# 1-Axis_Board_-_Camera_Gantry.net
KiCad netlist of a schematic drawn in EAGLE
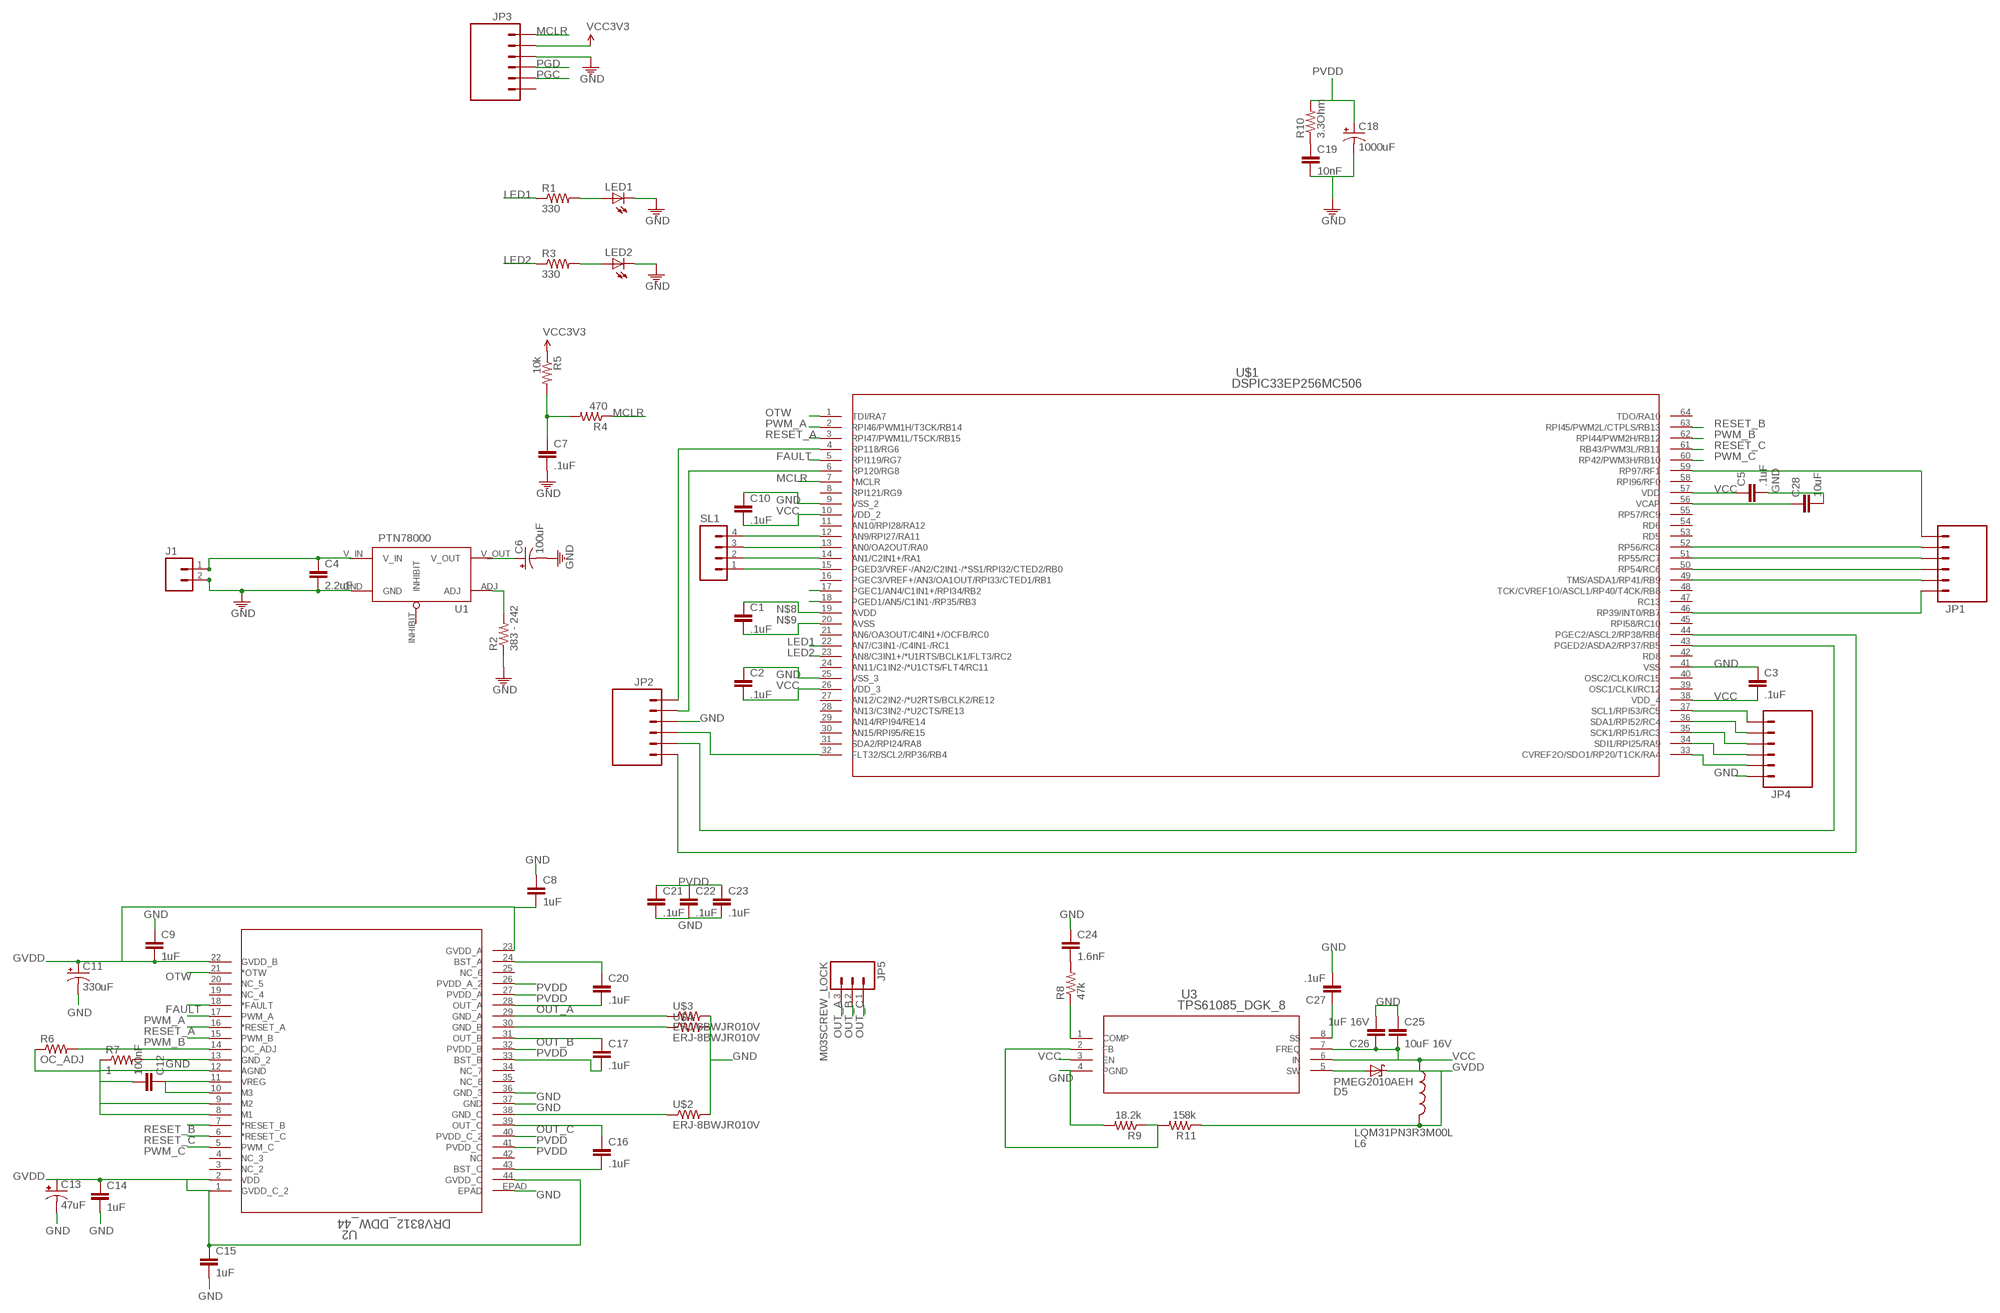
[diagram p0: schematic, sheet 1]

(export (version "E")
  (design (tool "Eeschema 10.0.6"))
  (components
    (comp (ref "C1")
      (value ".1uF")
      (footprint "eagle-import:0805")
      (libsource (lib "eagle-import") (part "CAP0805"))
    )
    (comp (ref "C2")
      (value ".1uF")
      (footprint "eagle-import:0805")
      (libsource (lib "eagle-import") (part "CAP0805"))
    )
    (comp (ref "C3")
      (value ".1uF")
      (footprint "eagle-import:0805")
      (libsource (lib "eagle-import") (part "CAP0805"))
    )
    (comp (ref "C4")
      (value "2.2uF")
      (footprint "eagle-import:1206")
      (libsource (lib "eagle-import") (part "CMPE118lib_CAP1206"))
    )
    (comp (ref "C5")
      (value ".1uF")
      (footprint "eagle-import:0805")
      (libsource (lib "eagle-import") (part "CAP0805"))
    )
    (comp (ref "C6")
      (value "100uF")
      (footprint "eagle-import:CPOL-RADIAL-100UF-25V")
      (libsource (lib "eagle-import") (part "CAP_POLPTH1"))
    )
    (comp (ref "C7")
      (value ".1uF")
      (footprint "eagle-import:0805")
      (libsource (lib "eagle-import") (part "CAP0805"))
    )
    (comp (ref "C8")
      (value "1uF")
      (footprint "eagle-import:0805")
      (libsource (lib "eagle-import") (part "CAP0805"))
    )
    (comp (ref "C9")
      (value "1uF")
      (footprint "eagle-import:0805")
      (libsource (lib "eagle-import") (part "CAP0805"))
    )
    (comp (ref "C10")
      (value ".1uF")
      (footprint "eagle-import:0805")
      (libsource (lib "eagle-import") (part "CAP0805"))
    )
    (comp (ref "C11")
      (value "330uF")
      (footprint "eagle-import:CPOL-RADIAL-1000UF-25V")
      (libsource (lib "eagle-import") (part "CAP_POLPTH4"))
    )
    (comp (ref "C12")
      (value "100nF")
      (footprint "eagle-import:0805")
      (libsource (lib "eagle-import") (part "CAP0805"))
    )
    (comp (ref "C13")
      (value "47uF")
      (footprint "eagle-import:CPOL-RADIAL-1000UF-25V")
      (libsource (lib "eagle-import") (part "CAP_POLPTH4"))
    )
    (comp (ref "C14")
      (value "1uF")
      (footprint "eagle-import:0805")
      (libsource (lib "eagle-import") (part "CAP0805"))
    )
    (comp (ref "C15")
      (value "1uF")
      (footprint "eagle-import:0805")
      (libsource (lib "eagle-import") (part "CAP0805"))
    )
    (comp (ref "C16")
      (value ".1uF")
      (footprint "eagle-import:0805")
      (libsource (lib "eagle-import") (part "CAP0805"))
    )
    (comp (ref "C17")
      (value ".1uF")
      (footprint "eagle-import:0805")
      (libsource (lib "eagle-import") (part "CAP0805"))
    )
    (comp (ref "C18")
      (value "1000uF")
      (footprint "eagle-import:CPOL-RADIAL-1000UF-25V")
      (libsource (lib "eagle-import") (part "CAP_POLPTH4"))
    )
    (comp (ref "C19")
      (value "10nF")
      (footprint "eagle-import:0805")
      (libsource (lib "eagle-import") (part "CAP0805"))
    )
    (comp (ref "C20")
      (value ".1uF")
      (footprint "eagle-import:0805")
      (libsource (lib "eagle-import") (part "CAP0805"))
    )
    (comp (ref "C21")
      (value ".1uF")
      (footprint "eagle-import:0805")
      (libsource (lib "eagle-import") (part "CAP0805"))
    )
    (comp (ref "C22")
      (value ".1uF")
      (footprint "eagle-import:0805")
      (libsource (lib "eagle-import") (part "CAP0805"))
    )
    (comp (ref "C23")
      (value ".1uF")
      (footprint "eagle-import:0805")
      (libsource (lib "eagle-import") (part "CAP0805"))
    )
    (comp (ref "C24")
      (value "1.6nF")
      (footprint "eagle-import:0805")
      (libsource (lib "eagle-import") (part "CAP0805"))
    )
    (comp (ref "C25")
      (value "10uF 16V")
      (footprint "eagle-import:1206")
      (libsource (lib "eagle-import") (part "CAP1206"))
    )
    (comp (ref "C26")
      (value "1uF 16V")
      (footprint "eagle-import:0805")
      (libsource (lib "eagle-import") (part "CAP0805"))
    )
    (comp (ref "C27")
      (value ".1uF")
      (footprint "eagle-import:0805")
      (libsource (lib "eagle-import") (part "CAP0805"))
    )
    (comp (ref "C28")
      (value "10uF")
      (footprint "eagle-import:1206")
      (libsource (lib "eagle-import") (part "CAP1206"))
    )
    (comp (ref "D5")
      (value "PMEG2010AEH")
      (footprint "eagle-import:SOD-123")
      (libsource (lib "eagle-import") (part "PMEG2010AEH"))
    )
    (comp (ref "J1")
      (value "M023.5MM-NO_SILK")
      (footprint "eagle-import:SCREWTERMINAL-3.5MM-2-NS")
      (libsource (lib "eagle-import") (part "M023.5MM-NO_SILK"))
    )
    (comp (ref "JP1")
      (value "M06LOCK")
      (footprint "eagle-import:1X06_LOCK")
      (libsource (lib "eagle-import") (part "M06LOCK"))
    )
    (comp (ref "JP2")
      (value "M06LOCK")
      (footprint "eagle-import:1X06_LOCK")
      (libsource (lib "eagle-import") (part "M06LOCK"))
    )
    (comp (ref "JP3")
      (value "M06LOCK")
      (footprint "eagle-import:1X06_LOCK")
      (libsource (lib "eagle-import") (part "CMPE118lib_M06LOCK"))
    )
    (comp (ref "JP4")
      (value "M06LOCK")
      (footprint "eagle-import:1X06_LOCK")
      (libsource (lib "eagle-import") (part "M06LOCK"))
    )
    (comp (ref "JP5")
      (value "M03SCREW_LOCK")
      (footprint "eagle-import:SCREWTERMINAL-3.5MM-3_LOCK.007S")
      (libsource (lib "eagle-import") (part "M03SCREW_LOCK"))
    )
    (comp (ref "L6")
      (value "LQM31PN3R3M00L")
      (footprint "eagle-import:1206")
      (libsource (lib "eagle-import") (part "LQM31PN3R3M00L"))
    )
    (comp (ref "LED1")
      (value "LED1206")
      (footprint "eagle-import:LED-1206")
      (fields (field (name "COLOR") "red"))
      (libsource (lib "eagle-import") (part "LED1206"))
    )
    (comp (ref "LED2")
      (value "LED1206")
      (footprint "eagle-import:LED-1206")
      (fields (field (name "COLOR") "red"))
      (libsource (lib "eagle-import") (part "LED1206"))
    )
    (comp (ref "R1")
      (value "330")
      (footprint "eagle-import:0805")
      (libsource (lib "eagle-import") (part "CMPE118lib_RESISTOR0805-RES"))
    )
    (comp (ref "R2")
      (value "383 - 242")
      (footprint "eagle-import:0805")
      (libsource (lib "eagle-import") (part "CMPE118lib_RESISTOR0805-RES"))
    )
    (comp (ref "R3")
      (value "330")
      (footprint "eagle-import:0805")
      (libsource (lib "eagle-import") (part "CMPE118lib_RESISTOR0805-RES"))
    )
    (comp (ref "R4")
      (value "470")
      (footprint "eagle-import:0805")
      (libsource (lib "eagle-import") (part "CMPE118lib_RESISTOR0805-RES"))
    )
    (comp (ref "R5")
      (value "10k")
      (footprint "eagle-import:0805")
      (libsource (lib "eagle-import") (part "CMPE118lib_RESISTOR0805-RES"))
    )
    (comp (ref "R6")
      (value "OC_ADJ")
      (footprint "eagle-import:0805")
      (libsource (lib "eagle-import") (part "RESISTOR0805-RES"))
    )
    (comp (ref "R7")
      (value "1")
      (footprint "eagle-import:0805")
      (libsource (lib "eagle-import") (part "RESISTOR0805-RES"))
    )
    (comp (ref "R8")
      (value "47k")
      (footprint "eagle-import:0805")
      (libsource (lib "eagle-import") (part "RESISTOR0805-RES"))
    )
    (comp (ref "R9")
      (value "18.2k")
      (footprint "eagle-import:0805")
      (libsource (lib "eagle-import") (part "RESISTOR0805-RES"))
    )
    (comp (ref "R10")
      (value "3.3Ohm")
      (footprint "eagle-import:0805")
      (libsource (lib "eagle-import") (part "RESISTOR0805-RES"))
    )
    (comp (ref "R11")
      (value "158k")
      (footprint "eagle-import:0805")
      (libsource (lib "eagle-import") (part "RESISTOR0805-RES"))
    )
    (comp (ref "SL1")
      (value "M04LOCK")
      (footprint "eagle-import:1X04_LOCK")
      (libsource (lib "eagle-import") (part "M04LOCK"))
    )
    (comp (ref "U$1")
      (value "DSPIC33EP256MC506")
      (footprint "eagle-import:QFP64-10X10MC")
      (libsource (lib "eagle-import") (part "DSPIC33EP256MC506"))
    )
    (comp (ref "U$2")
      (value "ERJ-8BWJR010V")
      (footprint "eagle-import:1206")
      (libsource (lib "eagle-import") (part "ERJ-8BWJR010V"))
    )
    (comp (ref "U$3")
      (value "ERJ-8BWJR010V")
      (footprint "eagle-import:1206")
      (libsource (lib "eagle-import") (part "ERJ-8BWJR010V"))
    )
    (comp (ref "U$4")
      (value "ERJ-8BWJR010V")
      (footprint "eagle-import:1206")
      (libsource (lib "eagle-import") (part "ERJ-8BWJR010V"))
    )
    (comp (ref "U1")
      (value "PTN78000")
      (footprint "eagle-import:PTN78000")
      (libsource (lib "eagle-import") (part "PTN78000THROUGH-HOLE"))
    )
    (comp (ref "U2")
      (value "DRV8312_DDW_44")
      (footprint "eagle-import:DDW44_8P26X4P31")
      (fields
        (field (name "GENERIC_PART_NUMBER") "DRV8312")
        (field (name "MANUFACTURER") "Texas Instruments")
        (field (name "MANUFACTURER_PART_NUMBER") "drv8312_ddw_44")
      )
      (libsource (lib "eagle-import") (part "DRV8312_DDW_44"))
    )
    (comp (ref "U3")
      (value "TPS61085_DGK_8")
      (footprint "eagle-import:DGK8")
      (fields
        (field (name "GENERIC_PART_NUMBER") "TPS61085")
        (field (name "MANUFACTURER") "Texas Instruments")
        (field (name "MANUFACTURER_PART_NUMBER") "tps61085_dgk_8")
      )
      (libsource (lib "eagle-import") (part "TPS61085_DGK_8"))
    )
  )
  (nets
    (net (code "1") (name "/FAULT") (class "Default")
      (node (ref "U$1") (pin "5") (pinfunction "RPI119/RG7_5") (pintype "passive"))
      (node (ref "U2") (pin "18") (pinfunction "*FAULT_18") (pintype "output"))
    )
    (net (code "2") (name "/GVDD") (class "Default")
      (node (ref "C11") (pin "1") (pinfunction "+_1") (pintype "passive"))
      (node (ref "C13") (pin "1") (pinfunction "+_1") (pintype "passive"))
      (node (ref "C14") (pin "1") (pinfunction "1_1") (pintype "passive"))
      (node (ref "C15") (pin "1") (pinfunction "1_1") (pintype "passive"))
      (node (ref "C8") (pin "2") (pinfunction "2_2") (pintype "passive"))
      (node (ref "C9") (pin "2") (pinfunction "2_2") (pintype "passive"))
      (node (ref "D5") (pin "C") (pinfunction "C_C") (pintype "passive"))
      (node (ref "L6") (pin "2") (pinfunction "2_2") (pintype "passive"))
      (node (ref "R11") (pin "1") (pinfunction "1_1") (pintype "passive"))
      (node (ref "U2") (pin "1") (pinfunction "GVDD_C_2_1") (pintype "power_in"))
      (node (ref "U2") (pin "2") (pinfunction "VDD_2") (pintype "power_in"))
      (node (ref "U2") (pin "22") (pinfunction "GVDD_B_22") (pintype "power_in"))
      (node (ref "U2") (pin "23") (pinfunction "GVDD_A_23") (pintype "power_in"))
      (node (ref "U2") (pin "44") (pinfunction "GVDD_C_44") (pintype "power_in"))
    )
    (net (code "3") (name "/LED1") (class "Default")
      (node (ref "R1") (pin "1") (pinfunction "1_1") (pintype "passive"))
      (node (ref "U$1") (pin "22") (pinfunction "AN7/C3IN1-/C4IN1-/RC1_22") (pintype "passive"))
    )
    (net (code "4") (name "/LED2") (class "Default")
      (node (ref "R3") (pin "1") (pinfunction "1_1") (pintype "passive"))
      (node (ref "U$1") (pin "23") (pinfunction "AN8/C3IN1+/*U1RTS/BCLK1/FLT3/RC2_23") (pintype "passive"))
    )
    (net (code "5") (name "/MCLR") (class "Default")
      (node (ref "JP3") (pin "1") (pinfunction "1_1") (pintype "passive"))
      (node (ref "R4") (pin "1") (pinfunction "1_1") (pintype "passive"))
      (node (ref "U$1") (pin "7") (pinfunction "*MCLR_7") (pintype "passive"))
    )
    (net (code "6") (name "/N$8") (class "Default")
      (node (ref "C1") (pin "1") (pinfunction "1_1") (pintype "passive"))
      (node (ref "U$1") (pin "19") (pinfunction "AVDD_19") (pintype "passive"))
    )
    (net (code "7") (name "/N$9") (class "Default")
      (node (ref "C1") (pin "2") (pinfunction "2_2") (pintype "passive"))
      (node (ref "U$1") (pin "20") (pinfunction "AVSS_20") (pintype "passive"))
    )
    (net (code "8") (name "/OTW") (class "Default")
      (node (ref "U$1") (pin "1") (pinfunction "TDI/RA7_1") (pintype "passive"))
      (node (ref "U2") (pin "21") (pinfunction "*OTW_21") (pintype "output"))
    )
    (net (code "9") (name "/OUT_A") (class "Default")
      (node (ref "C20") (pin "2") (pinfunction "2_2") (pintype "passive"))
      (node (ref "JP5") (pin "3") (pinfunction "3_3") (pintype "passive"))
      (node (ref "U2") (pin "28") (pinfunction "OUT_A_28") (pintype "output"))
    )
    (net (code "10") (name "/OUT_B") (class "Default")
      (node (ref "C17") (pin "1") (pinfunction "1_1") (pintype "passive"))
      (node (ref "JP5") (pin "2") (pinfunction "2_2") (pintype "passive"))
      (node (ref "U2") (pin "31") (pinfunction "OUT_B_31") (pintype "output"))
    )
    (net (code "11") (name "/OUT_C") (class "Default")
      (node (ref "C16") (pin "1") (pinfunction "1_1") (pintype "passive"))
      (node (ref "JP5") (pin "1") (pinfunction "1_1") (pintype "passive"))
      (node (ref "U2") (pin "39") (pinfunction "OUT_C_39") (pintype "output"))
    )
    (net (code "12") (name "/PGC") (class "Default")
      (node (ref "JP3") (pin "5") (pinfunction "5_5") (pintype "passive"))
      (node (ref "U$1") (pin "17") (pinfunction "PGEC1/AN4/C1IN1+/RPI34/RB2_17") (pintype "passive"))
    )
    (net (code "13") (name "/PGD") (class "Default")
      (node (ref "JP3") (pin "4") (pinfunction "4_4") (pintype "passive"))
      (node (ref "U$1") (pin "18") (pinfunction "PGED1/AN5/C1IN1-/RP35/RB3_18") (pintype "passive"))
    )
    (net (code "14") (name "/PVDD") (class "Default")
      (node (ref "C18") (pin "1") (pinfunction "+_1") (pintype "passive"))
      (node (ref "C21") (pin "1") (pinfunction "1_1") (pintype "passive"))
      (node (ref "C22") (pin "1") (pinfunction "1_1") (pintype "passive"))
      (node (ref "C23") (pin "1") (pinfunction "1_1") (pintype "passive"))
      (node (ref "C4") (pin "1") (pinfunction "1_1") (pintype "passive"))
      (node (ref "J1") (pin "1") (pinfunction "2_1") (pintype "passive"))
      (node (ref "R10") (pin "2") (pinfunction "2_2") (pintype "passive"))
      (node (ref "U1") (pin "V_IN") (pinfunction "V_IN_V_IN") (pintype "power_in"))
      (node (ref "U2") (pin "26") (pinfunction "PVDD_A_2_26") (pintype "power_in"))
      (node (ref "U2") (pin "27") (pinfunction "PVDD_A_27") (pintype "power_in"))
      (node (ref "U2") (pin "32") (pinfunction "PVDD_B_32") (pintype "power_in"))
      (node (ref "U2") (pin "40") (pinfunction "PVDD_C_2_40") (pintype "power_in"))
      (node (ref "U2") (pin "41") (pinfunction "PVDD_C_41") (pintype "power_in"))
    )
    (net (code "15") (name "/PWM_A") (class "Default")
      (node (ref "U$1") (pin "2") (pinfunction "RPI46/PWM1H/T3CK/RB14_2") (pintype "passive"))
      (node (ref "U2") (pin "17") (pinfunction "PWM_A_17") (pintype "input"))
    )
    (net (code "16") (name "/PWM_B") (class "Default")
      (node (ref "U$1") (pin "62") (pinfunction "RPI44/PWM2H/RB12_62") (pintype "passive"))
      (node (ref "U2") (pin "15") (pinfunction "PWM_B_15") (pintype "input"))
    )
    (net (code "17") (name "/PWM_C") (class "Default")
      (node (ref "U$1") (pin "60") (pinfunction "RP42/PWM3H/RB10_60") (pintype "passive"))
      (node (ref "U2") (pin "5") (pinfunction "PWM_C_5") (pintype "input"))
    )
    (net (code "18") (name "/RESET_A") (class "Default")
      (node (ref "U$1") (pin "3") (pinfunction "RPI47/PWM1L/T5CK/RB15_3") (pintype "passive"))
      (node (ref "U2") (pin "16") (pinfunction "*RESET_A_16") (pintype "input"))
    )
    (net (code "19") (name "/RESET_B") (class "Default")
      (node (ref "U$1") (pin "63") (pinfunction "RPI45/PWM2L/CTPLS/RB13_63") (pintype "passive"))
      (node (ref "U2") (pin "7") (pinfunction "*RESET_B_7") (pintype "input"))
    )
    (net (code "20") (name "/RESET_C") (class "Default")
      (node (ref "U$1") (pin "61") (pinfunction "RB43/PWM3L/RB11_61") (pintype "passive"))
      (node (ref "U2") (pin "6") (pinfunction "*RESET_C_6") (pintype "input"))
    )
    (net (code "21") (name "/VCC") (class "Default")
      (node (ref "C10") (pin "2") (pinfunction "2_2") (pintype "passive"))
      (node (ref "C2") (pin "2") (pinfunction "2_2") (pintype "passive"))
      (node (ref "C25") (pin "2") (pinfunction "2_2") (pintype "passive"))
      (node (ref "C26") (pin "1") (pinfunction "1_1") (pintype "passive"))
      (node (ref "C3") (pin "2") (pinfunction "2_2") (pintype "passive"))
      (node (ref "C5") (pin "1") (pinfunction "1_1") (pintype "passive"))
      (node (ref "C6") (pin "1") (pinfunction "+_1") (pintype "passive"))
      (node (ref "L6") (pin "1") (pinfunction "1_1") (pintype "passive"))
      (node (ref "U$1") (pin "10") (pinfunction "VDD_2_10") (pintype "passive"))
      (node (ref "U$1") (pin "26") (pinfunction "VDD_3_26") (pintype "passive"))
      (node (ref "U$1") (pin "38") (pinfunction "VDD_4_38") (pintype "passive"))
      (node (ref "U$1") (pin "57") (pinfunction "VDD_57") (pintype "passive"))
      (node (ref "U1") (pin "V_OUT") (pinfunction "V_OUT_V_OUT") (pintype "output"))
      (node (ref "U3") (pin "3") (pinfunction "EN_3") (pintype "input"))
      (node (ref "U3") (pin "6") (pinfunction "IN_6") (pintype "input"))
      (node (ref "U3") (pin "7") (pinfunction "FREQ_7") (pintype "input"))
    )
    (net (code "22") (name "GND") (class "Default")
      (node (ref "C10") (pin "1") (pinfunction "1_1") (pintype "passive"))
      (node (ref "C11") (pin "2") (pinfunction "-_2") (pintype "passive"))
      (node (ref "C13") (pin "2") (pinfunction "-_2") (pintype "passive"))
      (node (ref "C14") (pin "2") (pinfunction "2_2") (pintype "passive"))
      (node (ref "C15") (pin "2") (pinfunction "2_2") (pintype "passive"))
      (node (ref "C18") (pin "2") (pinfunction "-_2") (pintype "passive"))
      (node (ref "C19") (pin "2") (pinfunction "2_2") (pintype "passive"))
      (node (ref "C2") (pin "1") (pinfunction "1_1") (pintype "passive"))
      (node (ref "C21") (pin "2") (pinfunction "2_2") (pintype "passive"))
      (node (ref "C22") (pin "2") (pinfunction "2_2") (pintype "passive"))
      (node (ref "C23") (pin "2") (pinfunction "2_2") (pintype "passive"))
      (node (ref "C24") (pin "1") (pinfunction "1_1") (pintype "passive"))
      (node (ref "C25") (pin "1") (pinfunction "1_1") (pintype "passive"))
      (node (ref "C26") (pin "2") (pinfunction "2_2") (pintype "passive"))
      (node (ref "C27") (pin "2") (pinfunction "2_2") (pintype "passive"))
      (node (ref "C28") (pin "2") (pinfunction "2_2") (pintype "passive"))
      (node (ref "C3") (pin "1") (pinfunction "1_1") (pintype "passive"))
      (node (ref "C4") (pin "2") (pinfunction "2_2") (pintype "passive"))
      (node (ref "C5") (pin "2") (pinfunction "2_2") (pintype "passive"))
      (node (ref "C6") (pin "2") (pinfunction "-_2") (pintype "passive"))
      (node (ref "C7") (pin "2") (pinfunction "2_2") (pintype "passive"))
      (node (ref "C8") (pin "1") (pinfunction "1_1") (pintype "passive"))
      (node (ref "C9") (pin "1") (pinfunction "1_1") (pintype "passive"))
      (node (ref "J1") (pin "2") (pinfunction "1_2") (pintype "passive"))
      (node (ref "JP2") (pin "3") (pinfunction "3_3") (pintype "passive"))
      (node (ref "JP3") (pin "3") (pinfunction "3_3") (pintype "passive"))
      (node (ref "JP4") (pin "1") (pinfunction "1_1") (pintype "passive"))
      (node (ref "LED1") (pin "C") (pinfunction "C_C") (pintype "passive"))
      (node (ref "LED2") (pin "C") (pinfunction "C_C") (pintype "passive"))
      (node (ref "R2") (pin "1") (pinfunction "1_1") (pintype "passive"))
      (node (ref "R7") (pin "2") (pinfunction "2_2") (pintype "passive"))
      (node (ref "R9") (pin "2") (pinfunction "2_2") (pintype "passive"))
      (node (ref "U$1") (pin "25") (pinfunction "VSS_3_25") (pintype "passive"))
      (node (ref "U$1") (pin "41") (pinfunction "VSS_41") (pintype "passive"))
      (node (ref "U$1") (pin "9") (pinfunction "VSS_2_9") (pintype "passive"))
      (node (ref "U$2") (pin "2") (pinfunction "2_2") (pintype "passive"))
      (node (ref "U$3") (pin "2") (pinfunction "2_2") (pintype "passive"))
      (node (ref "U$4") (pin "2") (pinfunction "2_2") (pintype "passive"))
      (node (ref "U1") (pin "GND") (pinfunction "GND_GND") (pintype "power_in"))
      (node (ref "U2") (pin "13") (pinfunction "GND_2_13") (pintype "power_in"))
      (node (ref "U2") (pin "36") (pinfunction "GND_3_36") (pintype "power_in"))
      (node (ref "U2") (pin "37") (pinfunction "GND_37") (pintype "power_in"))
      (node (ref "U2") (pin "EPAD") (pinfunction "EPAD_EPAD") (pintype "passive"))
      (node (ref "U3") (pin "4") (pinfunction "PGND_4") (pintype "power_in"))
    )
    (net (code "23") (name "Net-(C7-Pad1)") (class "Default")
      (node (ref "C7") (pin "1") (pinfunction "1_1") (pintype "passive"))
      (node (ref "R4") (pin "2") (pinfunction "2_2") (pintype "passive"))
      (node (ref "R5") (pin "2") (pinfunction "2_2") (pintype "passive"))
    )
    (net (code "24") (name "Net-(C19-Pad1)") (class "Default")
      (node (ref "C19") (pin "1") (pinfunction "1_1") (pintype "passive"))
      (node (ref "R10") (pin "1") (pinfunction "1_1") (pintype "passive"))
    )
    (net (code "25") (name "Net-(C24-Pad2)") (class "Default")
      (node (ref "C24") (pin "2") (pinfunction "2_2") (pintype "passive"))
      (node (ref "R8") (pin "2") (pinfunction "2_2") (pintype "passive"))
    )
    (net (code "26") (name "Net-(LED1-PadA)") (class "Default")
      (node (ref "LED1") (pin "A") (pinfunction "A_A") (pintype "passive"))
      (node (ref "R1") (pin "2") (pinfunction "2_2") (pintype "passive"))
    )
    (net (code "27") (name "Net-(LED2-PadA)") (class "Default")
      (node (ref "LED2") (pin "A") (pinfunction "A_A") (pintype "passive"))
      (node (ref "R3") (pin "2") (pinfunction "2_2") (pintype "passive"))
    )
    (net (code "28") (name "Net-(R2-Pad2)") (class "Default")
      (node (ref "R2") (pin "2") (pinfunction "2_2") (pintype "passive"))
      (node (ref "U1") (pin "ADJ") (pinfunction "ADJ_ADJ") (pintype "input"))
    )
    (net (code "29") (name "Net-(U$1-AN0{slash}OA2OUT{slash}RA0)") (class "Default")
      (node (ref "SL1") (pin "3") (pinfunction "3_3") (pintype "passive"))
      (node (ref "U$1") (pin "13") (pinfunction "AN0/OA2OUT/RA0_13") (pintype "passive"))
    )
    (net (code "30") (name "Net-(U$1-AN1{slash}C2IN1+{slash}RA1)") (class "Default")
      (node (ref "SL1") (pin "2") (pinfunction "2_2") (pintype "passive"))
      (node (ref "U$1") (pin "14") (pinfunction "AN1/C2IN1+/RA1_14") (pintype "passive"))
    )
    (net (code "31") (name "Net-(U$1-AN9{slash}RPI27{slash}RA11)") (class "Default")
      (node (ref "SL1") (pin "4") (pinfunction "4_4") (pintype "passive"))
      (node (ref "U$1") (pin "12") (pinfunction "AN9/RPI27/RA11_12") (pintype "passive"))
    )
    (net (code "32") (name "Net-(U$1-CVREF2O{slash}SDO1{slash}RP20{slash}T1CK{slash}RA4)") (class "Default")
      (node (ref "JP4") (pin "2") (pinfunction "2_2") (pintype "passive"))
      (node (ref "U$1") (pin "33") (pinfunction "CVREF2O/SDO1/RP20/T1CK/RA4_33") (pintype "passive"))
    )
    (net (code "33") (name "Net-(U$1-FLT32{slash}SCL2{slash}RP36{slash}RB4)") (class "Default")
      (node (ref "JP2") (pin "4") (pinfunction "4_4") (pintype "passive"))
      (node (ref "U$1") (pin "32") (pinfunction "FLT32/SCL2/RP36/RB4_32") (pintype "passive"))
    )
    (net (code "34") (name "Net-(U$1-PGEC2{slash}ASCL2{slash}RP38{slash}RB6)") (class "Default")
      (node (ref "JP2") (pin "6") (pinfunction "6_6") (pintype "passive"))
      (node (ref "U$1") (pin "44") (pinfunction "PGEC2/ASCL2/RP38/RB6_44") (pintype "passive"))
    )
    (net (code "35") (name "Net-(U$1-PGED2{slash}ASDA2{slash}RP37{slash}RB5)") (class "Default")
      (node (ref "JP2") (pin "5") (pinfunction "5_5") (pintype "passive"))
      (node (ref "U$1") (pin "43") (pinfunction "PGED2/ASDA2/RP37/RB5_43") (pintype "passive"))
    )
    (net (code "36") (name "Net-(U$1-PGED3{slash}VREF-{slash}AN2{slash}C2IN1-{slash}*SS1{slash}RPI32{slash}CTED2{slash}RB0)") (class "Default")
      (node (ref "SL1") (pin "1") (pinfunction "1_1") (pintype "passive"))
      (node (ref "U$1") (pin "15") (pinfunction "PGED3/VREF-/AN2/C2IN1-/*SS1/RPI32/CTED2/RB0_15") (pintype "passive"))
    )
    (net (code "37") (name "Net-(U$1-RP39{slash}INT0{slash}RB7)") (class "Default")
      (node (ref "JP1") (pin "1") (pinfunction "1_1") (pintype "passive"))
      (node (ref "U$1") (pin "46") (pinfunction "RP39/INT0/RB7_46") (pintype "passive"))
    )
    (net (code "38") (name "Net-(U$1-RP54{slash}RC6)") (class "Default")
      (node (ref "JP1") (pin "3") (pinfunction "3_3") (pintype "passive"))
      (node (ref "U$1") (pin "50") (pinfunction "RP54/RC6_50") (pintype "passive"))
    )
    (net (code "39") (name "Net-(U$1-RP55{slash}RC7)") (class "Default")
      (node (ref "JP1") (pin "4") (pinfunction "4_4") (pintype "passive"))
      (node (ref "U$1") (pin "51") (pinfunction "RP55/RC7_51") (pintype "passive"))
    )
    (net (code "40") (name "Net-(U$1-RP56{slash}RC8)") (class "Default")
      (node (ref "JP1") (pin "5") (pinfunction "5_5") (pintype "passive"))
      (node (ref "U$1") (pin "52") (pinfunction "RP56/RC8_52") (pintype "passive"))
    )
    (net (code "41") (name "Net-(U$1-RP97{slash}RF1)") (class "Default")
      (node (ref "JP1") (pin "6") (pinfunction "6_6") (pintype "passive"))
      (node (ref "U$1") (pin "59") (pinfunction "RP97/RF1_59") (pintype "passive"))
    )
    (net (code "42") (name "Net-(U$1-RP118{slash}RG6)") (class "Default")
      (node (ref "JP2") (pin "1") (pinfunction "1_1") (pintype "passive"))
      (node (ref "U$1") (pin "4") (pinfunction "RP118/RG6_4") (pintype "passive"))
    )
    (net (code "43") (name "Net-(U$1-RP120{slash}RG8)") (class "Default")
      (node (ref "JP2") (pin "2") (pinfunction "2_2") (pintype "passive"))
      (node (ref "U$1") (pin "6") (pinfunction "RP120/RG8_6") (pintype "passive"))
    )
    (net (code "44") (name "Net-(U$1-SCK1{slash}RPI51{slash}RC3)") (class "Default")
      (node (ref "JP4") (pin "4") (pinfunction "4_4") (pintype "passive"))
      (node (ref "U$1") (pin "35") (pinfunction "SCK1/RPI51/RC3_35") (pintype "passive"))
    )
    (net (code "45") (name "Net-(U$1-SCL1{slash}RPI53{slash}RC5)") (class "Default")
      (node (ref "JP4") (pin "6") (pinfunction "6_6") (pintype "passive"))
      (node (ref "U$1") (pin "37") (pinfunction "SCL1/RPI53/RC5_37") (pintype "passive"))
    )
    (net (code "46") (name "Net-(U$1-SDA1{slash}RPI52{slash}RC4)") (class "Default")
      (node (ref "JP4") (pin "5") (pinfunction "5_5") (pintype "passive"))
      (node (ref "U$1") (pin "36") (pinfunction "SDA1/RPI52/RC4_36") (pintype "passive"))
    )
    (net (code "47") (name "Net-(U$1-SDI1{slash}RPI25{slash}RA9)") (class "Default")
      (node (ref "JP4") (pin "3") (pinfunction "3_3") (pintype "passive"))
      (node (ref "U$1") (pin "34") (pinfunction "SDI1/RPI25/RA9_34") (pintype "passive"))
    )
    (net (code "48") (name "Net-(U$1-TMS{slash}ASDA1{slash}RP41{slash}RB9)") (class "Default")
      (node (ref "JP1") (pin "2") (pinfunction "2_2") (pintype "passive"))
      (node (ref "U$1") (pin "49") (pinfunction "TMS/ASDA1/RP41/RB9_49") (pintype "passive"))
    )
    (net (code "49") (name "Net-(U$1-VCAP)") (class "Default")
      (node (ref "C28") (pin "1") (pinfunction "1_1") (pintype "passive"))
      (node (ref "U$1") (pin "56") (pinfunction "VCAP_56") (pintype "passive"))
    )
    (net (code "50") (name "Net-(U2-AGND)") (class "Default")
      (node (ref "C12") (pin "2") (pinfunction "2_2") (pintype "passive"))
      (node (ref "R6") (pin "1") (pinfunction "1_1") (pintype "passive"))
      (node (ref "R7") (pin "1") (pinfunction "1_1") (pintype "passive"))
      (node (ref "U2") (pin "12") (pinfunction "AGND_12") (pintype "power_in"))
      (node (ref "U2") (pin "8") (pinfunction "M1_8") (pintype "input"))
      (node (ref "U2") (pin "9") (pinfunction "M2_9") (pintype "input"))
    )
    (net (code "51") (name "Net-(U2-BST_A)") (class "Default")
      (node (ref "C20") (pin "1") (pinfunction "1_1") (pintype "passive"))
      (node (ref "U2") (pin "24") (pinfunction "BST_A_24") (pintype "power_in"))
    )
    (net (code "52") (name "Net-(U2-BST_B)") (class "Default")
      (node (ref "C17") (pin "2") (pinfunction "2_2") (pintype "passive"))
      (node (ref "U2") (pin "33") (pinfunction "BST_B_33") (pintype "power_in"))
    )
    (net (code "53") (name "Net-(U2-BST_C)") (class "Default")
      (node (ref "C16") (pin "2") (pinfunction "2_2") (pintype "passive"))
      (node (ref "U2") (pin "43") (pinfunction "BST_C_43") (pintype "power_in"))
    )
    (net (code "54") (name "Net-(U2-GND_A)") (class "Default")
      (node (ref "U$3") (pin "1") (pinfunction "1_1") (pintype "passive"))
      (node (ref "U2") (pin "29") (pinfunction "GND_A_29") (pintype "power_in"))
    )
    (net (code "55") (name "Net-(U2-GND_B)") (class "Default")
      (node (ref "U$4") (pin "1") (pinfunction "1_1") (pintype "passive"))
      (node (ref "U2") (pin "30") (pinfunction "GND_B_30") (pintype "power_in"))
    )
    (net (code "56") (name "Net-(U2-GND_C)") (class "Default")
      (node (ref "U$2") (pin "1") (pinfunction "1_1") (pintype "passive"))
      (node (ref "U2") (pin "38") (pinfunction "GND_C_38") (pintype "power_in"))
    )
    (net (code "57") (name "Net-(U2-M3)") (class "Default")
      (node (ref "C12") (pin "1") (pinfunction "1_1") (pintype "passive"))
      (node (ref "U2") (pin "10") (pinfunction "M3_10") (pintype "input"))
      (node (ref "U2") (pin "11") (pinfunction "VREG_11") (pintype "power_in"))
    )
    (net (code "58") (name "Net-(U2-OC_ADJ)") (class "Default")
      (node (ref "R6") (pin "2") (pinfunction "2_2") (pintype "passive"))
      (node (ref "U2") (pin "14") (pinfunction "OC_ADJ_14") (pintype "output"))
    )
    (net (code "59") (name "Net-(U3-COMP)") (class "Default")
      (node (ref "R8") (pin "1") (pinfunction "1_1") (pintype "passive"))
      (node (ref "U3") (pin "1") (pinfunction "COMP_1") (pintype "passive"))
    )
    (net (code "60") (name "Net-(U3-FB)") (class "Default")
      (node (ref "R11") (pin "2") (pinfunction "2_2") (pintype "passive"))
      (node (ref "R9") (pin "1") (pinfunction "1_1") (pintype "passive"))
      (node (ref "U3") (pin "2") (pinfunction "FB_2") (pintype "input"))
    )
    (net (code "61") (name "Net-(U3-SS)") (class "Default")
      (node (ref "C27") (pin "1") (pinfunction "1_1") (pintype "passive"))
      (node (ref "U3") (pin "8") (pinfunction "SS_8") (pintype "passive"))
    )
    (net (code "62") (name "Net-(U3-SW)") (class "Default")
      (node (ref "D5") (pin "A") (pinfunction "A_A") (pintype "passive"))
      (node (ref "U3") (pin "5") (pinfunction "SW_5") (pintype "passive"))
    )
    (net (code "63") (name "VCC3V3") (class "Default")
      (node (ref "JP3") (pin "2") (pinfunction "2_2") (pintype "passive"))
      (node (ref "R5") (pin "1") (pinfunction "1_1") (pintype "passive"))
    )
    (net (code "64") (name "unconnected-(JP3-Pad6)") (class "Default")
      (node (ref "JP3") (pin "6") (pinfunction "6_6") (pintype "passive"))
    )
    (net (code "65") (name "unconnected-(U$1-AN6{slash}OA3OUT{slash}C4IN1+{slash}OCFB{slash}RC0-Pad21)") (class "Default")
      (node (ref "U$1") (pin "21") (pinfunction "AN6/OA3OUT/C4IN1+/OCFB/RC0_21") (pintype "passive"))
    )
    (net (code "66") (name "unconnected-(U$1-AN10{slash}RPI28{slash}RA12-Pad11)") (class "Default")
      (node (ref "U$1") (pin "11") (pinfunction "AN10/RPI28/RA12_11") (pintype "passive"))
    )
    (net (code "67") (name "unconnected-(U$1-AN11{slash}C1IN2-{slash}*U1CTS{slash}FLT4{slash}RC11-Pad24)") (class "Default")
      (node (ref "U$1") (pin "24") (pinfunction "AN11/C1IN2-/*U1CTS/FLT4/RC11_24") (pintype "passive"))
    )
    (net (code "68") (name "unconnected-(U$1-AN12{slash}C2IN2-{slash}*U2RTS{slash}BCLK2{slash}RE12-Pad27)") (class "Default")
      (node (ref "U$1") (pin "27") (pinfunction "AN12/C2IN2-/*U2RTS/BCLK2/RE12_27") (pintype "passive"))
    )
    (net (code "69") (name "unconnected-(U$1-AN13{slash}C3IN2-{slash}*U2CTS{slash}RE13-Pad28)") (class "Default")
      (node (ref "U$1") (pin "28") (pinfunction "AN13/C3IN2-/*U2CTS/RE13_28") (pintype "passive"))
    )
    (net (code "70") (name "unconnected-(U$1-AN14{slash}RPI94{slash}RE14-Pad29)") (class "Default")
      (node (ref "U$1") (pin "29") (pinfunction "AN14/RPI94/RE14_29") (pintype "passive"))
    )
    (net (code "71") (name "unconnected-(U$1-AN15{slash}RPI95{slash}RE15-Pad30)") (class "Default")
      (node (ref "U$1") (pin "30") (pinfunction "AN15/RPI95/RE15_30") (pintype "passive"))
    )
    (net (code "72") (name "unconnected-(U$1-OSC1{slash}CLKI{slash}RC12-Pad39)") (class "Default")
      (node (ref "U$1") (pin "39") (pinfunction "OSC1/CLKI/RC12_39") (pintype "passive"))
    )
    (net (code "73") (name "unconnected-(U$1-OSC2{slash}CLKO{slash}RC15-Pad40)") (class "Default")
      (node (ref "U$1") (pin "40") (pinfunction "OSC2/CLKO/RC15_40") (pintype "passive"))
    )
    (net (code "74") (name "unconnected-(U$1-PGEC3{slash}VREF+{slash}AN3{slash}OA1OUT{slash}RPI33{slash}CTED1{slash}RB1-Pad16)") (class "Default")
      (node (ref "U$1") (pin "16") (pinfunction "PGEC3/VREF+/AN3/OA1OUT/RPI33/CTED1/RB1_16") (pintype "passive"))
    )
    (net (code "75") (name "unconnected-(U$1-RC13-Pad47)") (class "Default")
      (node (ref "U$1") (pin "47") (pinfunction "RC13_47") (pintype "passive"))
    )
    (net (code "76") (name "unconnected-(U$1-RD5-Pad53)") (class "Default")
      (node (ref "U$1") (pin "53") (pinfunction "RD5_53") (pintype "passive"))
    )
    (net (code "77") (name "unconnected-(U$1-RD6-Pad54)") (class "Default")
      (node (ref "U$1") (pin "54") (pinfunction "RD6_54") (pintype "passive"))
    )
    (net (code "78") (name "unconnected-(U$1-RD8-Pad42)") (class "Default")
      (node (ref "U$1") (pin "42") (pinfunction "RD8_42") (pintype "passive"))
    )
    (net (code "79") (name "unconnected-(U$1-RP57{slash}RC9-Pad55)") (class "Default")
      (node (ref "U$1") (pin "55") (pinfunction "RP57/RC9_55") (pintype "passive"))
    )
    (net (code "80") (name "unconnected-(U$1-RPI58{slash}RC10-Pad45)") (class "Default")
      (node (ref "U$1") (pin "45") (pinfunction "RPI58/RC10_45") (pintype "passive"))
    )
    (net (code "81") (name "unconnected-(U$1-RPI96{slash}RF0-Pad58)") (class "Default")
      (node (ref "U$1") (pin "58") (pinfunction "RPI96/RF0_58") (pintype "passive"))
    )
    (net (code "82") (name "unconnected-(U$1-RPI121{slash}RG9-Pad8)") (class "Default")
      (node (ref "U$1") (pin "8") (pinfunction "RPI121/RG9_8") (pintype "passive"))
    )
    (net (code "83") (name "unconnected-(U$1-SDA2{slash}RPI24{slash}RA8-Pad31)") (class "Default")
      (node (ref "U$1") (pin "31") (pinfunction "SDA2/RPI24/RA8_31") (pintype "passive"))
    )
    (net (code "84") (name "unconnected-(U$1-TCK{slash}CVREF1O{slash}ASCL1{slash}RP40{slash}T4CK{slash}RB8-Pad48)") (class "Default")
      (node (ref "U$1") (pin "48") (pinfunction "TCK/CVREF1O/ASCL1/RP40/T4CK/RB8_48") (pintype "passive"))
    )
    (net (code "85") (name "unconnected-(U$1-TDO{slash}RA10-Pad64)") (class "Default")
      (node (ref "U$1") (pin "64") (pinfunction "TDO/RA10_64") (pintype "passive"))
    )
    (net (code "86") (name "unconnected-(U1-PadINHIBIT)") (class "Default")
      (node (ref "U1") (pin "INHIBIT") (pinfunction "INHIBIT_INHIBIT") (pintype "input"))
    )
    (net (code "87") (name "unconnected-(U2-NC-Pad42)") (class "Default")
      (node (ref "U2") (pin "42") (pinfunction "NC_42") (pintype "passive"))
    )
    (net (code "88") (name "unconnected-(U2-NC_2-Pad3)") (class "Default")
      (node (ref "U2") (pin "3") (pinfunction "NC_2_3") (pintype "passive"))
    )
    (net (code "89") (name "unconnected-(U2-NC_3-Pad4)") (class "Default")
      (node (ref "U2") (pin "4") (pinfunction "NC_3_4") (pintype "passive"))
    )
    (net (code "90") (name "unconnected-(U2-NC_4-Pad19)") (class "Default")
      (node (ref "U2") (pin "19") (pinfunction "NC_4_19") (pintype "passive"))
    )
    (net (code "91") (name "unconnected-(U2-NC_5-Pad20)") (class "Default")
      (node (ref "U2") (pin "20") (pinfunction "NC_5_20") (pintype "passive"))
    )
    (net (code "92") (name "unconnected-(U2-NC_6-Pad25)") (class "Default")
      (node (ref "U2") (pin "25") (pinfunction "NC_6_25") (pintype "passive"))
    )
    (net (code "93") (name "unconnected-(U2-NC_7-Pad34)") (class "Default")
      (node (ref "U2") (pin "34") (pinfunction "NC_7_34") (pintype "passive"))
    )
    (net (code "94") (name "unconnected-(U2-NC_8-Pad35)") (class "Default")
      (node (ref "U2") (pin "35") (pinfunction "NC_8_35") (pintype "passive"))
    )
  )
)
